# Schematic.net
KiCad netlist of a schematic drawn in Altium Designer
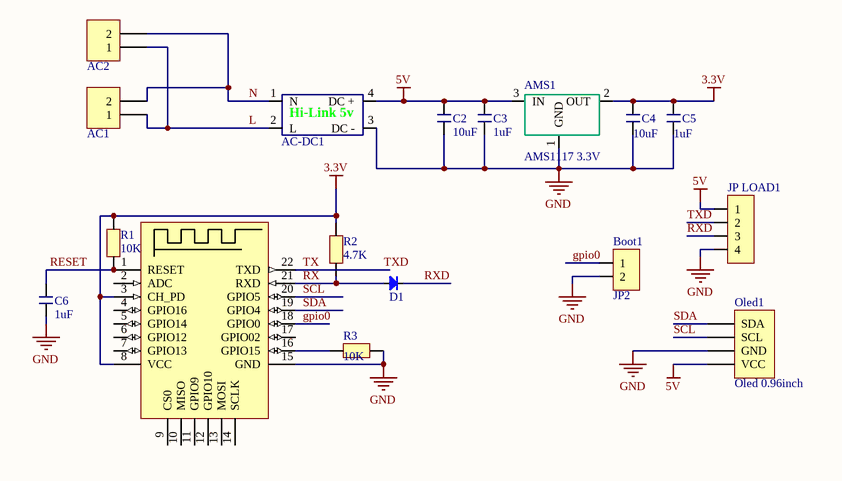
[diagram p0: Schematic.SchDoc]

(export (version "E")
  (design (tool "Eeschema 10.0.6"))
  (components
    (comp (ref "AC-DC1")
      (value "Hi-link 5v")
      (footprint "Hi-Link")
      (libsource (lib "library") (part "Hi-link 5v"))
    )
    (comp (ref "AC1")
      (value "KF2")
      (footprint "KF2-5.08")
      (fields
        (field (name "MANUFACTURER") "Würth Elektronik eiSos GmbH")
        (field (name "PARTNO") "691103110002")
        (field (name "CREATED BY") "Karrer Zheng")
      )
      (libsource (lib "LIBRARY") (part "KF2"))
    )
    (comp (ref "AC2")
      (value "KF2")
      (footprint "KF2-5.08")
      (fields
        (field (name "MANUFACTURER") "Würth Elektronik eiSos GmbH")
        (field (name "PARTNO") "691103110002")
        (field (name "CREATED BY") "Karrer Zheng")
      )
      (libsource (lib "LIBRARY") (part "KF2"))
    )
    (comp (ref "AMS1")
      (value "AMS1117 3.3V")
      (footprint "AMS-1117")
      (libsource (lib "library") (part "AMS1117 3.3V"))
    )
    (comp (ref "Boot1")
      (value "JP2")
      (footprint "JP2-D1T")
      (description "WR-PHD 2.54 mm Angled Socket Header")
      (fields
        (field (name "MANUFACTURER") "Würth Elektronik eiSos GmbH")
        (field (name "PARTNO") "613002143121")
        (field (name "CREATED BY") "Karrer Zheng")
      )
      (libsource (lib "LIBRARY") (part "JP2"))
    )
    (comp (ref "C2")
      (value "10uF")
      (footprint "0805")
      (description "0603 SMD CAP")
      (libsource (lib "library") (part "C104 SMD"))
    )
    (comp (ref "C3")
      (value "1uF")
      (footprint "0805")
      (description "0603 SMD CAP")
      (libsource (lib "library") (part "C104 SMD"))
    )
    (comp (ref "C4")
      (value "10uF")
      (footprint "0805")
      (description "0603 SMD CAP")
      (libsource (lib "library") (part "C104 SMD"))
    )
    (comp (ref "C5")
      (value "1uF")
      (footprint "0805")
      (description "0603 SMD CAP")
      (libsource (lib "library") (part "C104 SMD"))
    )
    (comp (ref "C6")
      (value "1uF")
      (footprint "Cty1:0805")
      (description "0603 SMD CAP")
      (libsource (lib "library") (part "C104 SMD"))
    )
    (comp (ref "D1")
      (value "Diode")
      (footprint "DIO-1AN")
      (description "Default Diode")
      (fields (field (name "PUBLISHER") "Altium Limited"))
      (libsource (lib "LIBRARY") (part "Diode"))
    )
    (comp (ref "JP LOAD1")
      (value "JP4")
      (footprint "JP4-D1C")
      (description "WR-PHD 2.54 mm Angled Socket Header")
      (fields
        (field (name "MANUFACTURER") "Würth Elektronik eiSos GmbH")
        (field (name "PARTNO") "613004143121")
        (field (name "CREATED BY") "Karrer Zheng")
      )
      (libsource (lib "LIBRARY") (part "JP4"))
    )
    (comp (ref "MCU1") (value "~") (footprint "pw:Esp12") (libsource (lib "library") (part "ESP12F")))
    (comp (ref "Oled1")
      (value "Oled 0.96inch")
      (footprint "Oled 0.96")
      (libsource (lib "library") (part "Oled 0.96inch"))
    )
    (comp (ref "R1") (value "10K") (footprint "0805") (libsource (lib "library") (part "0603 Res")))
    (comp (ref "R2") (value "4.7K") (footprint "0805") (libsource (lib "library") (part "0603 Res")))
    (comp (ref "R3") (value "10K") (footprint "0805") (libsource (lib "") (part "0603 Res_1")))
  )
  (nets
    (net (code "1") (name "/L") (class "Default")
      (node (ref "AC-DC1") (pin "2") (pinfunction "L_2") (pintype "passive"))
      (node (ref "AC1") (pin "1") (pinfunction "1_1") (pintype "passive"))
      (node (ref "AC2") (pin "1") (pinfunction "1_1") (pintype "passive"))
    )
    (net (code "2") (name "/N") (class "Default")
      (node (ref "AC-DC1") (pin "1") (pinfunction "N_1") (pintype "passive"))
      (node (ref "AC1") (pin "2") (pinfunction "2_2") (pintype "passive"))
      (node (ref "AC2") (pin "2") (pinfunction "2_2") (pintype "passive"))
    )
    (net (code "3") (name "/RESET") (class "Default")
      (node (ref "C6") (pin "1") (pinfunction "1_1") (pintype "passive"))
      (node (ref "MCU1") (pin "1") (pinfunction "RESET_1") (pintype "passive"))
      (node (ref "R1") (pin "1") (pinfunction "1_1") (pintype "passive"))
    )
    (net (code "4") (name "/RX") (class "Default")
      (node (ref "D1") (pin "1") (pinfunction "A_1") (pintype "passive"))
      (node (ref "MCU1") (pin "21") (pinfunction "RXD_21") (pintype "input"))
      (node (ref "R2") (pin "1") (pinfunction "1_1") (pintype "passive"))
    )
    (net (code "5") (name "/RXD") (class "Default")
      (node (ref "D1") (pin "2") (pinfunction "K_2") (pintype "passive"))
      (node (ref "JP LOAD1") (pin "3") (pinfunction "3_3") (pintype "passive"))
    )
    (net (code "6") (name "/SCL") (class "Default")
      (node (ref "MCU1") (pin "20") (pinfunction "GPIO5_20") (pintype "bidirectional"))
      (node (ref "Oled1") (pin "3") (pinfunction "SCL_3") (pintype "passive"))
    )
    (net (code "7") (name "/SDA") (class "Default")
      (node (ref "MCU1") (pin "19") (pinfunction "GPIO4_19") (pintype "bidirectional"))
      (node (ref "Oled1") (pin "4") (pinfunction "SDA_4") (pintype "passive"))
    )
    (net (code "8") (name "/TX") (class "Default")
      (node (ref "JP LOAD1") (pin "2") (pinfunction "2_2") (pintype "passive"))
      (node (ref "MCU1") (pin "22") (pinfunction "TXD_22") (pintype "output"))
    )
    (net (code "9") (name "/gpio0") (class "Default")
      (node (ref "Boot1") (pin "1") (pinfunction "1_1") (pintype "passive"))
      (node (ref "MCU1") (pin "18") (pinfunction "GPIO0_18") (pintype "bidirectional"))
    )
    (net (code "10") (name "3.3V") (class "Default")
      (node (ref "AMS1") (pin "2") (pinfunction "OUT_2") (pintype "passive"))
      (node (ref "C4") (pin "1") (pinfunction "1_1") (pintype "passive"))
      (node (ref "C5") (pin "1") (pinfunction "1_1") (pintype "passive"))
      (node (ref "MCU1") (pin "3") (pinfunction "CH_PD_3") (pintype "input"))
      (node (ref "MCU1") (pin "8") (pinfunction "VCC_8") (pintype "passive"))
      (node (ref "R1") (pin "2") (pinfunction "2_2") (pintype "passive"))
      (node (ref "R2") (pin "2") (pinfunction "2_2") (pintype "passive"))
    )
    (net (code "11") (name "5V") (class "Default")
      (node (ref "AC-DC1") (pin "4") (pinfunction "DC_+_4") (pintype "passive"))
      (node (ref "AMS1") (pin "3") (pinfunction "IN_3") (pintype "passive"))
      (node (ref "C2") (pin "1") (pinfunction "1_1") (pintype "passive"))
      (node (ref "C3") (pin "1") (pinfunction "1_1") (pintype "passive"))
      (node (ref "JP LOAD1") (pin "1") (pinfunction "1_1") (pintype "passive"))
      (node (ref "Oled1") (pin "1") (pinfunction "VCC_1") (pintype "passive"))
    )
    (net (code "12") (name "GND") (class "Default")
      (node (ref "AC-DC1") (pin "3") (pinfunction "DC_-_3") (pintype "passive"))
      (node (ref "AMS1") (pin "1") (pinfunction "GND_1") (pintype "passive"))
      (node (ref "Boot1") (pin "2") (pinfunction "2_2") (pintype "passive"))
      (node (ref "C2") (pin "2") (pinfunction "2_2") (pintype "passive"))
      (node (ref "C3") (pin "2") (pinfunction "2_2") (pintype "passive"))
      (node (ref "C4") (pin "2") (pinfunction "2_2") (pintype "passive"))
      (node (ref "C5") (pin "2") (pinfunction "2_2") (pintype "passive"))
      (node (ref "C6") (pin "2") (pinfunction "2_2") (pintype "passive"))
      (node (ref "JP LOAD1") (pin "4") (pinfunction "4_4") (pintype "passive"))
      (node (ref "MCU1") (pin "15") (pinfunction "GND_15") (pintype "passive"))
      (node (ref "Oled1") (pin "2") (pinfunction "GND_2") (pintype "passive"))
      (node (ref "R3") (pin "2") (pinfunction "2_2") (pintype "passive"))
    )
    (net (code "13") (name "Net-(MCU1-GPIO15)") (class "Default")
      (node (ref "MCU1") (pin "16") (pinfunction "GPIO15_16") (pintype "bidirectional"))
      (node (ref "R3") (pin "1") (pinfunction "1_1") (pintype "passive"))
    )
    (net (code "14") (name "unconnected-(MCU1-ADC-Pad2)") (class "Default")
      (node (ref "MCU1") (pin "2") (pinfunction "ADC_2") (pintype "input"))
    )
    (net (code "15") (name "unconnected-(MCU1-CS0-Pad9)") (class "Default")
      (node (ref "MCU1") (pin "9") (pinfunction "CS0_9") (pintype "passive"))
    )
    (net (code "16") (name "unconnected-(MCU1-GPIO02-Pad17)") (class "Default")
      (node (ref "MCU1") (pin "17") (pinfunction "GPIO02_17") (pintype "bidirectional"))
    )
    (net (code "17") (name "unconnected-(MCU1-GPIO9-Pad11)") (class "Default")
      (node (ref "MCU1") (pin "11") (pinfunction "GPIO9_11") (pintype "passive"))
    )
    (net (code "18") (name "unconnected-(MCU1-GPIO10-Pad12)") (class "Default")
      (node (ref "MCU1") (pin "12") (pinfunction "GPIO10_12") (pintype "passive"))
    )
    (net (code "19") (name "unconnected-(MCU1-GPIO12-Pad6)") (class "Default")
      (node (ref "MCU1") (pin "6") (pinfunction "GPIO12_6") (pintype "bidirectional"))
    )
    (net (code "20") (name "unconnected-(MCU1-GPIO13-Pad7)") (class "Default")
      (node (ref "MCU1") (pin "7") (pinfunction "GPIO13_7") (pintype "bidirectional"))
    )
    (net (code "21") (name "unconnected-(MCU1-GPIO14-Pad5)") (class "Default")
      (node (ref "MCU1") (pin "5") (pinfunction "GPIO14_5") (pintype "bidirectional"))
    )
    (net (code "22") (name "unconnected-(MCU1-GPIO16-Pad4)") (class "Default")
      (node (ref "MCU1") (pin "4") (pinfunction "GPIO16_4") (pintype "bidirectional"))
    )
    (net (code "23") (name "unconnected-(MCU1-MISO-Pad10)") (class "Default")
      (node (ref "MCU1") (pin "10") (pinfunction "MISO_10") (pintype "passive"))
    )
    (net (code "24") (name "unconnected-(MCU1-MOSI-Pad13)") (class "Default")
      (node (ref "MCU1") (pin "13") (pinfunction "MOSI_13") (pintype "passive"))
    )
    (net (code "25") (name "unconnected-(MCU1-SCLK-Pad14)") (class "Default")
      (node (ref "MCU1") (pin "14") (pinfunction "SCLK_14") (pintype "passive"))
    )
  )
)
